# rs232_12V_step_Vadim_list2.net
KiCad netlist of a schematic drawn in Altium Designer
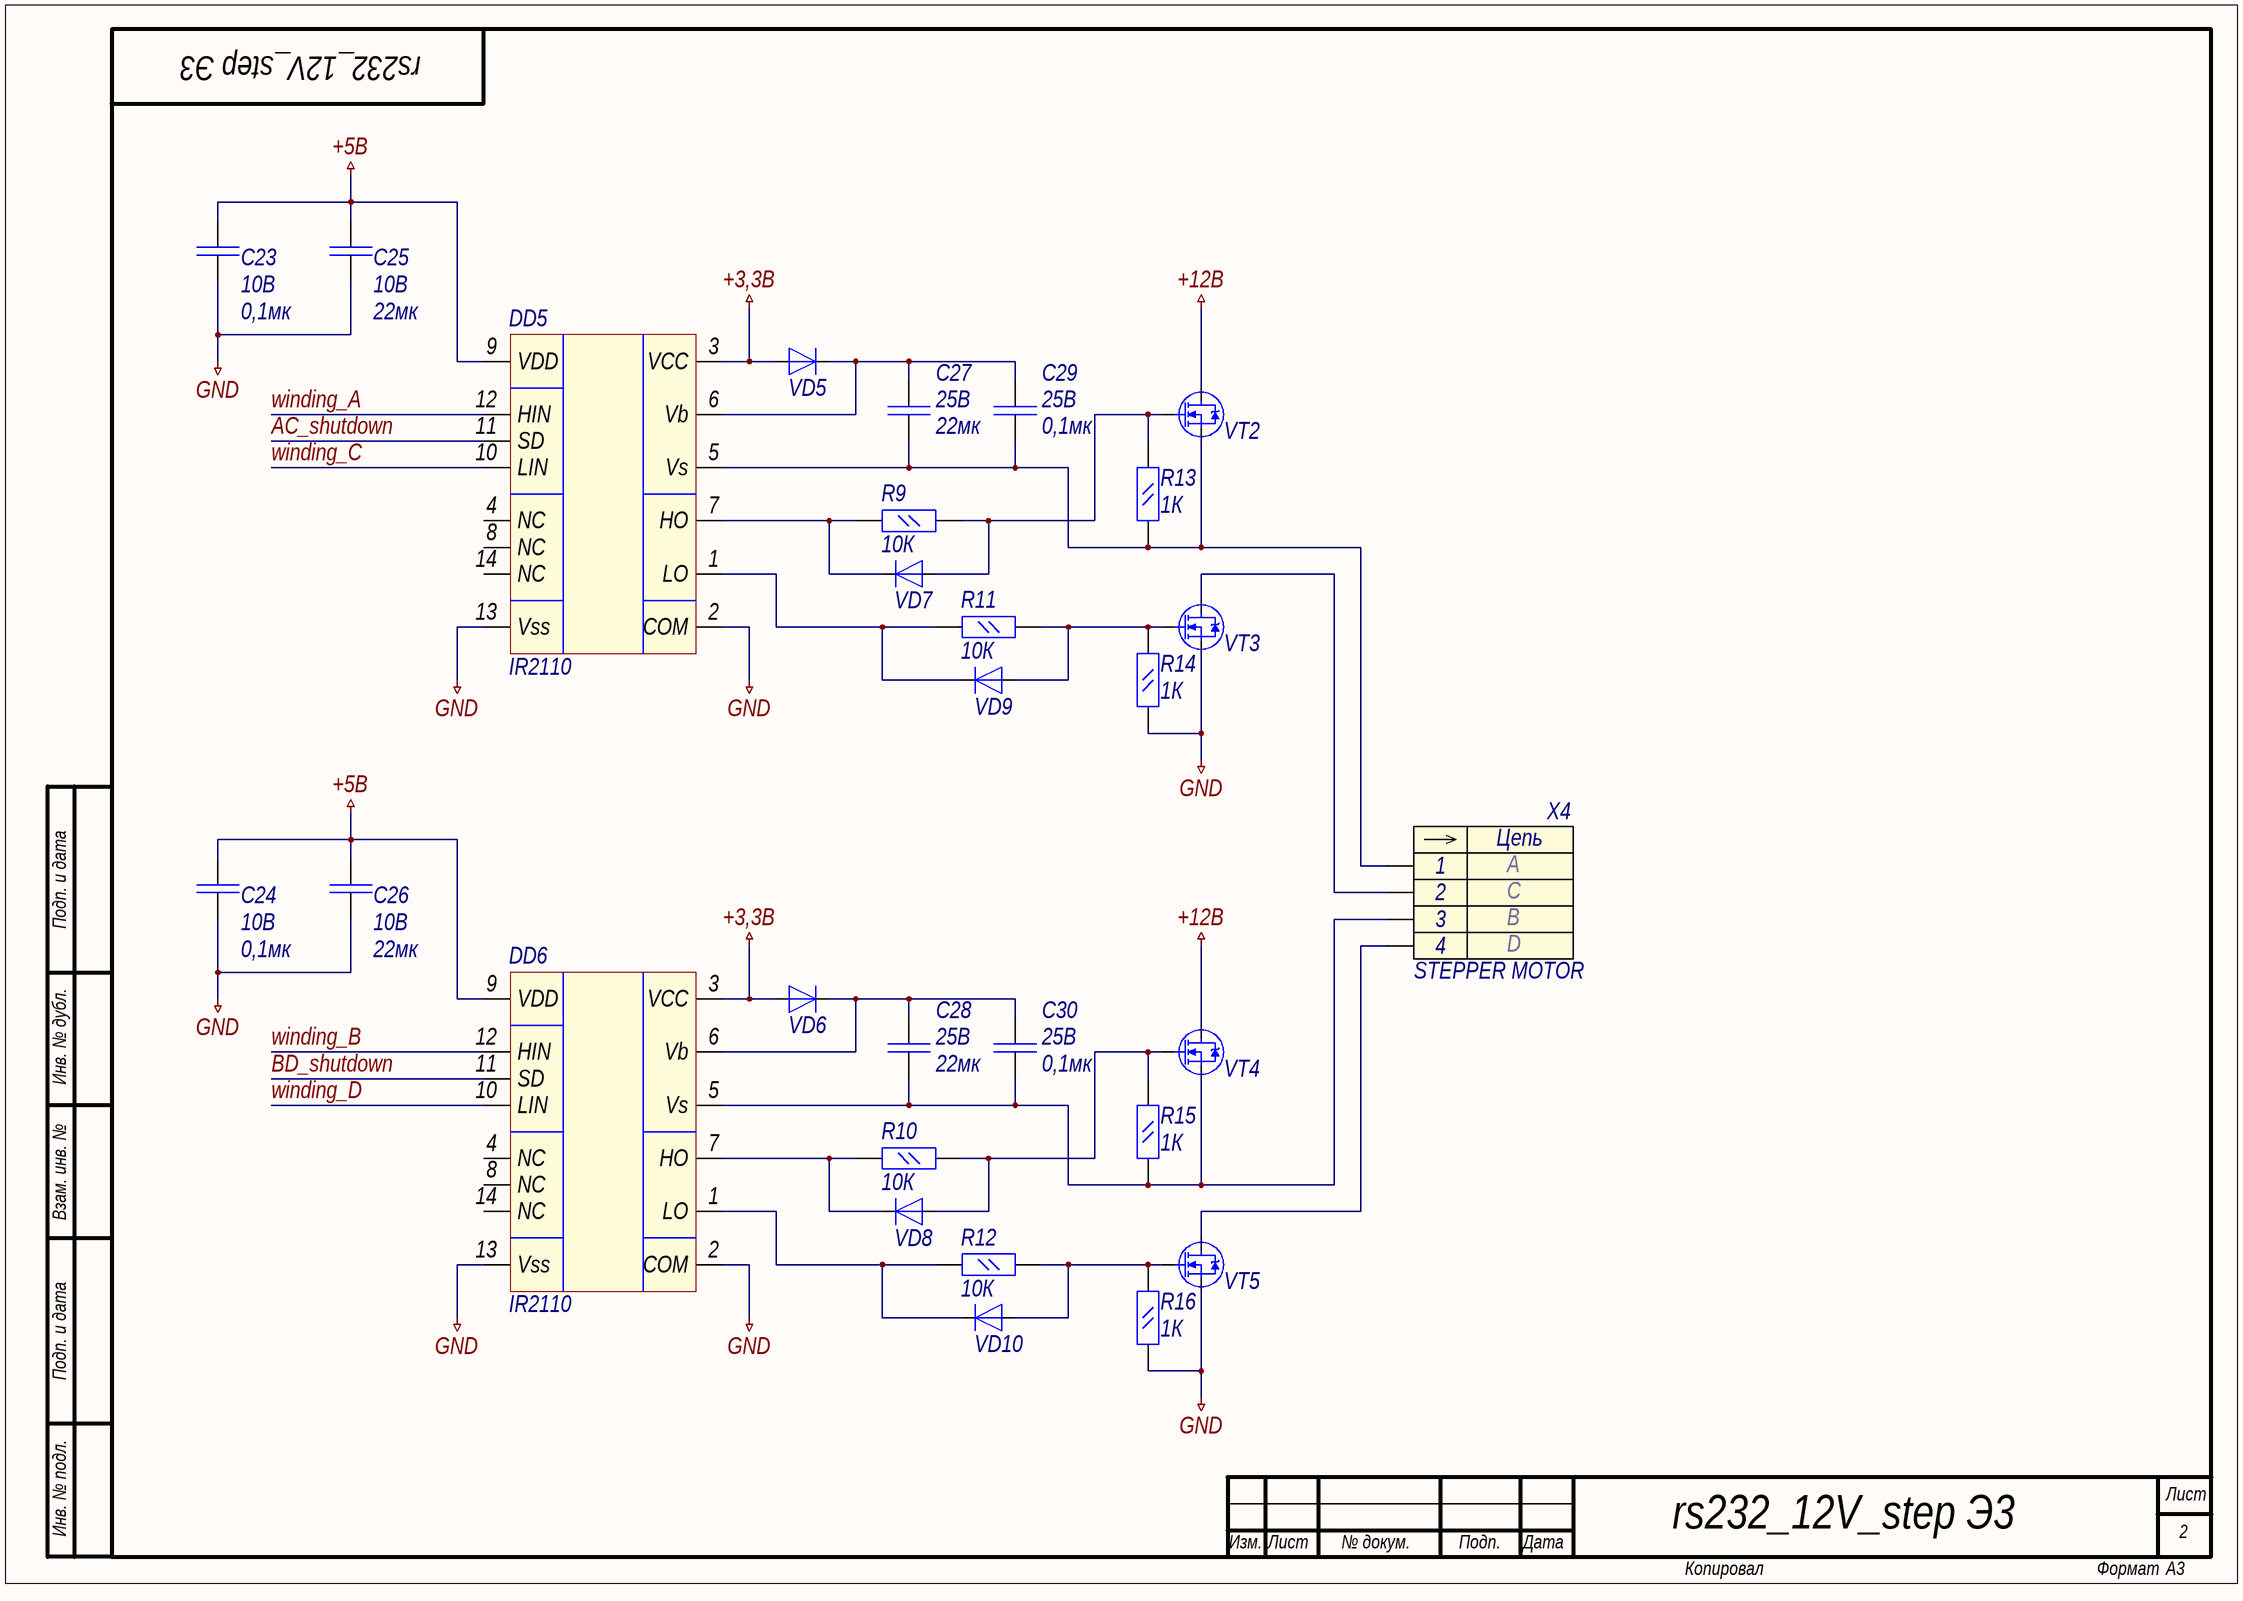
[diagram p0: rs232_12V_step_Vadim_list2.SchDoc]

(export (version "E")
  (design (tool "Eeschema 10.0.6"))
  (components
    (comp (ref "C23")
      (value "Capacitor")
      (footprint "CH0402C")
      (fields (field (name "VOLTAGE") "10В") (field (name "CAPACITANCE") "0,1мк"))
      (libsource (lib "GOST_Capacitors") (part "Capacitor"))
    )
    (comp (ref "C24")
      (value "Capacitor")
      (footprint "CH0402C")
      (fields (field (name "VOLTAGE") "10В") (field (name "CAPACITANCE") "0,1мк"))
      (libsource (lib "GOST_Capacitors") (part "Capacitor"))
    )
    (comp (ref "C25")
      (value "Capacitor")
      (footprint "CH0603C")
      (fields (field (name "VOLTAGE") "10В") (field (name "CAPACITANCE") "22мк"))
      (libsource (lib "GOST_Capacitors") (part "Capacitor"))
    )
    (comp (ref "C26")
      (value "Capacitor")
      (footprint "CH0603C")
      (fields (field (name "VOLTAGE") "10В") (field (name "CAPACITANCE") "22мк"))
      (libsource (lib "GOST_Capacitors") (part "Capacitor"))
    )
    (comp (ref "C27")
      (value "Capacitor")
      (footprint "CH0805C")
      (fields (field (name "VOLTAGE") "25В") (field (name "CAPACITANCE") "22мк"))
      (libsource (lib "GOST_Capacitors") (part "Capacitor"))
    )
    (comp (ref "C28")
      (value "Capacitor")
      (footprint "CH0805C")
      (fields (field (name "VOLTAGE") "25В") (field (name "CAPACITANCE") "22мк"))
      (libsource (lib "GOST_Capacitors") (part "Capacitor"))
    )
    (comp (ref "C29")
      (value "Capacitor")
      (footprint "CH0402C")
      (fields (field (name "VOLTAGE") "25В") (field (name "CAPACITANCE") "0,1мк"))
      (libsource (lib "GOST_Capacitors") (part "Capacitor"))
    )
    (comp (ref "C30")
      (value "Capacitor")
      (footprint "CH0402C")
      (fields (field (name "VOLTAGE") "25В") (field (name "CAPACITANCE") "0,1мк"))
      (libsource (lib "GOST_Capacitors") (part "Capacitor"))
    )
    (comp (ref "DD5")
      (value "IR2110")
      (footprint "14-DIP")
      (libsource (lib "GOST_lib_devices") (part "IR2110"))
    )
    (comp (ref "DD6")
      (value "IR2110")
      (footprint "14-DIP")
      (libsource (lib "GOST_lib_devices") (part "IR2110"))
    )
    (comp (ref "R9")
      (value "Res_0.125")
      (footprint "CH0805R")
      (fields (field (name "IMPEDANCE") "10К"))
      (libsource (lib "GOST_Resistors") (part "Res_0.125"))
    )
    (comp (ref "R10")
      (value "Res_0.125")
      (footprint "CH0805R")
      (fields (field (name "IMPEDANCE") "10К"))
      (libsource (lib "GOST_Resistors") (part "Res_0.125"))
    )
    (comp (ref "R11")
      (value "Res_0.125")
      (footprint "CH0805R")
      (fields (field (name "IMPEDANCE") "10К"))
      (libsource (lib "GOST_Resistors") (part "Res_0.125"))
    )
    (comp (ref "R12")
      (value "Res_0.125")
      (footprint "CH0805R")
      (fields (field (name "IMPEDANCE") "10К"))
      (libsource (lib "GOST_Resistors") (part "Res_0.125"))
    )
    (comp (ref "R13")
      (value "Res_0.125")
      (footprint "CH0402R")
      (fields (field (name "IMPEDANCE") "1К"))
      (libsource (lib "GOST_Resistors") (part "Res_0.125"))
    )
    (comp (ref "R14")
      (value "Res_0.125")
      (footprint "CH0402R")
      (fields (field (name "IMPEDANCE") "1К"))
      (libsource (lib "GOST_Resistors") (part "Res_0.125"))
    )
    (comp (ref "R15")
      (value "Res_0.125")
      (footprint "CH0402R")
      (fields (field (name "IMPEDANCE") "1К"))
      (libsource (lib "GOST_Resistors") (part "Res_0.125"))
    )
    (comp (ref "R16")
      (value "Res_0.125")
      (footprint "CH0402R")
      (fields (field (name "IMPEDANCE") "1К"))
      (libsource (lib "GOST_Resistors") (part "Res_0.125"))
    )
    (comp (ref "VD5") (value "Diod") (footprint "DO201AD") (libsource (lib "GOST_Diodes") (part "Diod")))
    (comp (ref "VD6") (value "Diod") (footprint "DO201AD") (libsource (lib "GOST_Diodes") (part "Diod")))
    (comp (ref "VD7") (value "Diod") (footprint "DO201AD") (libsource (lib "GOST_Diodes") (part "Diod")))
    (comp (ref "VD8") (value "Diod") (footprint "DO201AD") (libsource (lib "GOST_Diodes") (part "Diod")))
    (comp (ref "VD9") (value "Diod") (footprint "DO201AD") (libsource (lib "GOST_Diodes") (part "Diod")))
    (comp (ref "VD10") (value "Diod") (footprint "DO201AD") (libsource (lib "GOST_Diodes") (part "Diod")))
    (comp (ref "VT2")
      (value "N-Channel")
      (footprint "SOT23_132")
      (libsource (lib "GOST_Transistors") (part "N-Channel"))
    )
    (comp (ref "VT3")
      (value "N-Channel")
      (footprint "SOT23_132")
      (libsource (lib "GOST_Transistors") (part "N-Channel"))
    )
    (comp (ref "VT4")
      (value "N-Channel")
      (footprint "SOT23_132")
      (libsource (lib "GOST_Transistors") (part "N-Channel"))
    )
    (comp (ref "VT5")
      (value "N-Channel")
      (footprint "SOT23_132")
      (libsource (lib "GOST_Transistors") (part "N-Channel"))
    )
    (comp (ref "X4")
      (value "STEPPER MOTOR")
      (footprint "CON: CWF-4R")
      (description "Bipolar Stepper Motor 200 Step 0.35A 12VDC")
      (fields (field (name "2") "C") (field (name "3") "B") (field (name "1") "A") (field (name "4") "D"))
      (libsource (lib "GOST_lib_connectors") (part "4_pins"))
    )
  )
  (nets
    (net (code "1") (name "+3,3В") (class "Default")
      (node (ref "DD5") (pin "3") (pinfunction "VCC_3") (pintype "power_in"))
      (node (ref "DD6") (pin "3") (pinfunction "VCC_3") (pintype "power_in"))
      (node (ref "VD5") (pin "1") (pintype "passive"))
      (node (ref "VD6") (pin "1") (pintype "passive"))
    )
    (net (code "2") (name "+5В") (class "Default")
      (node (ref "C23") (pin "2") (pinfunction "C1-_2") (pintype "power_in"))
      (node (ref "C24") (pin "2") (pinfunction "C1-_2") (pintype "power_in"))
      (node (ref "C25") (pin "2") (pinfunction "C1-_2") (pintype "power_in"))
      (node (ref "C26") (pin "2") (pinfunction "C1-_2") (pintype "power_in"))
      (node (ref "DD5") (pin "9") (pinfunction "VDD_9") (pintype "power_in"))
      (node (ref "DD6") (pin "9") (pinfunction "VDD_9") (pintype "power_in"))
    )
    (net (code "3") (name "+12В") (class "Default")
      (node (ref "VT2") (pin "2") (pinfunction "D_2") (pintype "passive"))
      (node (ref "VT4") (pin "2") (pinfunction "D_2") (pintype "passive"))
    )
    (net (code "4") (name "/AC_shutdown") (class "Default")
      (node (ref "DD5") (pin "11") (pinfunction "SD_11") (pintype "power_in"))
    )
    (net (code "5") (name "/BD_shutdown") (class "Default")
      (node (ref "DD6") (pin "11") (pinfunction "SD_11") (pintype "power_in"))
    )
    (net (code "6") (name "/winding_A") (class "Default")
      (node (ref "DD5") (pin "12") (pinfunction "HIN_12") (pintype "power_in"))
    )
    (net (code "7") (name "/winding_B") (class "Default")
      (node (ref "DD6") (pin "12") (pinfunction "HIN_12") (pintype "power_in"))
    )
    (net (code "8") (name "/winding_C") (class "Default")
      (node (ref "DD5") (pin "10") (pinfunction "LIN_10") (pintype "power_in"))
    )
    (net (code "9") (name "/winding_D") (class "Default")
      (node (ref "DD6") (pin "10") (pinfunction "LIN_10") (pintype "power_in"))
    )
    (net (code "10") (name "GND") (class "Default")
      (node (ref "C23") (pin "1") (pinfunction "C1+_1") (pintype "power_in"))
      (node (ref "C24") (pin "1") (pinfunction "C1+_1") (pintype "power_in"))
      (node (ref "C25") (pin "1") (pinfunction "C1+_1") (pintype "power_in"))
      (node (ref "C26") (pin "1") (pinfunction "C1+_1") (pintype "power_in"))
      (node (ref "DD5") (pin "13") (pinfunction "Vss_13") (pintype "power_in"))
      (node (ref "DD5") (pin "2") (pinfunction "COM_2") (pintype "power_in"))
      (node (ref "DD6") (pin "13") (pinfunction "Vss_13") (pintype "power_in"))
      (node (ref "DD6") (pin "2") (pinfunction "COM_2") (pintype "power_in"))
      (node (ref "R14") (pin "2") (pinfunction "C1-_2") (pintype "power_in"))
      (node (ref "R16") (pin "2") (pinfunction "C1-_2") (pintype "power_in"))
      (node (ref "VT3") (pin "3") (pinfunction "S_3") (pintype "passive"))
      (node (ref "VT5") (pin "3") (pinfunction "S_3") (pintype "passive"))
    )
    (net (code "11") (name "Net-(C27-C1+)") (class "Default")
      (node (ref "C27") (pin "1") (pinfunction "C1+_1") (pintype "power_in"))
      (node (ref "C29") (pin "1") (pinfunction "C1+_1") (pintype "power_in"))
      (node (ref "DD5") (pin "5") (pinfunction "Vs_5") (pintype "power_in"))
      (node (ref "R13") (pin "2") (pinfunction "C1-_2") (pintype "power_in"))
      (node (ref "VT2") (pin "3") (pinfunction "S_3") (pintype "passive"))
      (node (ref "X4") (pin "1") (pinfunction "1_1") (pintype "passive"))
    )
    (net (code "12") (name "Net-(C27-C1-)") (class "Default")
      (node (ref "C27") (pin "2") (pinfunction "C1-_2") (pintype "power_in"))
      (node (ref "C29") (pin "2") (pinfunction "C1-_2") (pintype "power_in"))
      (node (ref "DD5") (pin "6") (pinfunction "Vb_6") (pintype "power_in"))
      (node (ref "VD5") (pin "2") (pintype "passive"))
    )
    (net (code "13") (name "Net-(C28-C1+)") (class "Default")
      (node (ref "C28") (pin "1") (pinfunction "C1+_1") (pintype "power_in"))
      (node (ref "C30") (pin "1") (pinfunction "C1+_1") (pintype "power_in"))
      (node (ref "DD6") (pin "5") (pinfunction "Vs_5") (pintype "power_in"))
      (node (ref "R15") (pin "2") (pinfunction "C1-_2") (pintype "power_in"))
      (node (ref "VT4") (pin "3") (pinfunction "S_3") (pintype "passive"))
      (node (ref "X4") (pin "3") (pinfunction "3_3") (pintype "passive"))
    )
    (net (code "14") (name "Net-(C28-C1-)") (class "Default")
      (node (ref "C28") (pin "2") (pinfunction "C1-_2") (pintype "power_in"))
      (node (ref "C30") (pin "2") (pinfunction "C1-_2") (pintype "power_in"))
      (node (ref "DD6") (pin "6") (pinfunction "Vb_6") (pintype "power_in"))
      (node (ref "VD6") (pin "2") (pintype "passive"))
    )
    (net (code "15") (name "Net-(DD5-HO)") (class "Default")
      (node (ref "DD5") (pin "7") (pinfunction "HO_7") (pintype "power_in"))
      (node (ref "R9") (pin "1") (pinfunction "C1-_1") (pintype "power_in"))
      (node (ref "VD7") (pin "2") (pintype "passive"))
    )
    (net (code "16") (name "Net-(DD5-LO)") (class "Default")
      (node (ref "DD5") (pin "1") (pinfunction "LO_1") (pintype "power_in"))
      (node (ref "R11") (pin "1") (pinfunction "C1-_1") (pintype "power_in"))
      (node (ref "VD9") (pin "2") (pintype "passive"))
    )
    (net (code "17") (name "Net-(DD6-HO)") (class "Default")
      (node (ref "DD6") (pin "7") (pinfunction "HO_7") (pintype "power_in"))
      (node (ref "R10") (pin "1") (pinfunction "C1-_1") (pintype "power_in"))
      (node (ref "VD8") (pin "2") (pintype "passive"))
    )
    (net (code "18") (name "Net-(DD6-LO)") (class "Default")
      (node (ref "DD6") (pin "1") (pinfunction "LO_1") (pintype "power_in"))
      (node (ref "R12") (pin "1") (pinfunction "C1-_1") (pintype "power_in"))
      (node (ref "VD10") (pin "2") (pintype "passive"))
    )
    (net (code "19") (name "Net-(VT2-G)") (class "Default")
      (node (ref "R13") (pin "1") (pinfunction "C1-_1") (pintype "power_in"))
      (node (ref "R9") (pin "2") (pinfunction "C1-_2") (pintype "power_in"))
      (node (ref "VD7") (pin "1") (pintype "passive"))
      (node (ref "VT2") (pin "1") (pinfunction "G_1") (pintype "passive"))
    )
    (net (code "20") (name "Net-(VT3-D)") (class "Default")
      (node (ref "VT3") (pin "2") (pinfunction "D_2") (pintype "passive"))
      (node (ref "X4") (pin "2") (pinfunction "2_2") (pintype "passive"))
    )
    (net (code "21") (name "Net-(VT3-G)") (class "Default")
      (node (ref "R11") (pin "2") (pinfunction "C1-_2") (pintype "power_in"))
      (node (ref "R14") (pin "1") (pinfunction "C1-_1") (pintype "power_in"))
      (node (ref "VD9") (pin "1") (pintype "passive"))
      (node (ref "VT3") (pin "1") (pinfunction "G_1") (pintype "passive"))
    )
    (net (code "22") (name "Net-(VT4-G)") (class "Default")
      (node (ref "R10") (pin "2") (pinfunction "C1-_2") (pintype "power_in"))
      (node (ref "R15") (pin "1") (pinfunction "C1-_1") (pintype "power_in"))
      (node (ref "VD8") (pin "1") (pintype "passive"))
      (node (ref "VT4") (pin "1") (pinfunction "G_1") (pintype "passive"))
    )
    (net (code "23") (name "Net-(VT5-D)") (class "Default")
      (node (ref "VT5") (pin "2") (pinfunction "D_2") (pintype "passive"))
      (node (ref "X4") (pin "4") (pinfunction "4_4") (pintype "passive"))
    )
    (net (code "24") (name "Net-(VT5-G)") (class "Default")
      (node (ref "R12") (pin "2") (pinfunction "C1-_2") (pintype "power_in"))
      (node (ref "R16") (pin "1") (pinfunction "C1-_1") (pintype "power_in"))
      (node (ref "VD10") (pin "1") (pintype "passive"))
      (node (ref "VT5") (pin "1") (pinfunction "G_1") (pintype "passive"))
    )
    (net (code "25") (name "unconnected-(DD5-NC-Pad4)") (class "Default")
      (node (ref "DD5") (pin "4") (pinfunction "NC_4") (pintype "power_in"))
    )
    (net (code "26") (name "unconnected-(DD5-NC-Pad8)") (class "Default")
      (node (ref "DD5") (pin "8") (pinfunction "NC_8") (pintype "power_in"))
    )
    (net (code "27") (name "unconnected-(DD5-NC-Pad14)") (class "Default")
      (node (ref "DD5") (pin "14") (pinfunction "NC_14") (pintype "power_in"))
    )
    (net (code "28") (name "unconnected-(DD6-NC-Pad4)") (class "Default")
      (node (ref "DD6") (pin "4") (pinfunction "NC_4") (pintype "power_in"))
    )
    (net (code "29") (name "unconnected-(DD6-NC-Pad8)") (class "Default")
      (node (ref "DD6") (pin "8") (pinfunction "NC_8") (pintype "power_in"))
    )
    (net (code "30") (name "unconnected-(DD6-NC-Pad14)") (class "Default")
      (node (ref "DD6") (pin "14") (pinfunction "NC_14") (pintype "power_in"))
    )
  )
)
